# SD_Board.net
KiCad netlist of a schematic drawn in Altium Designer
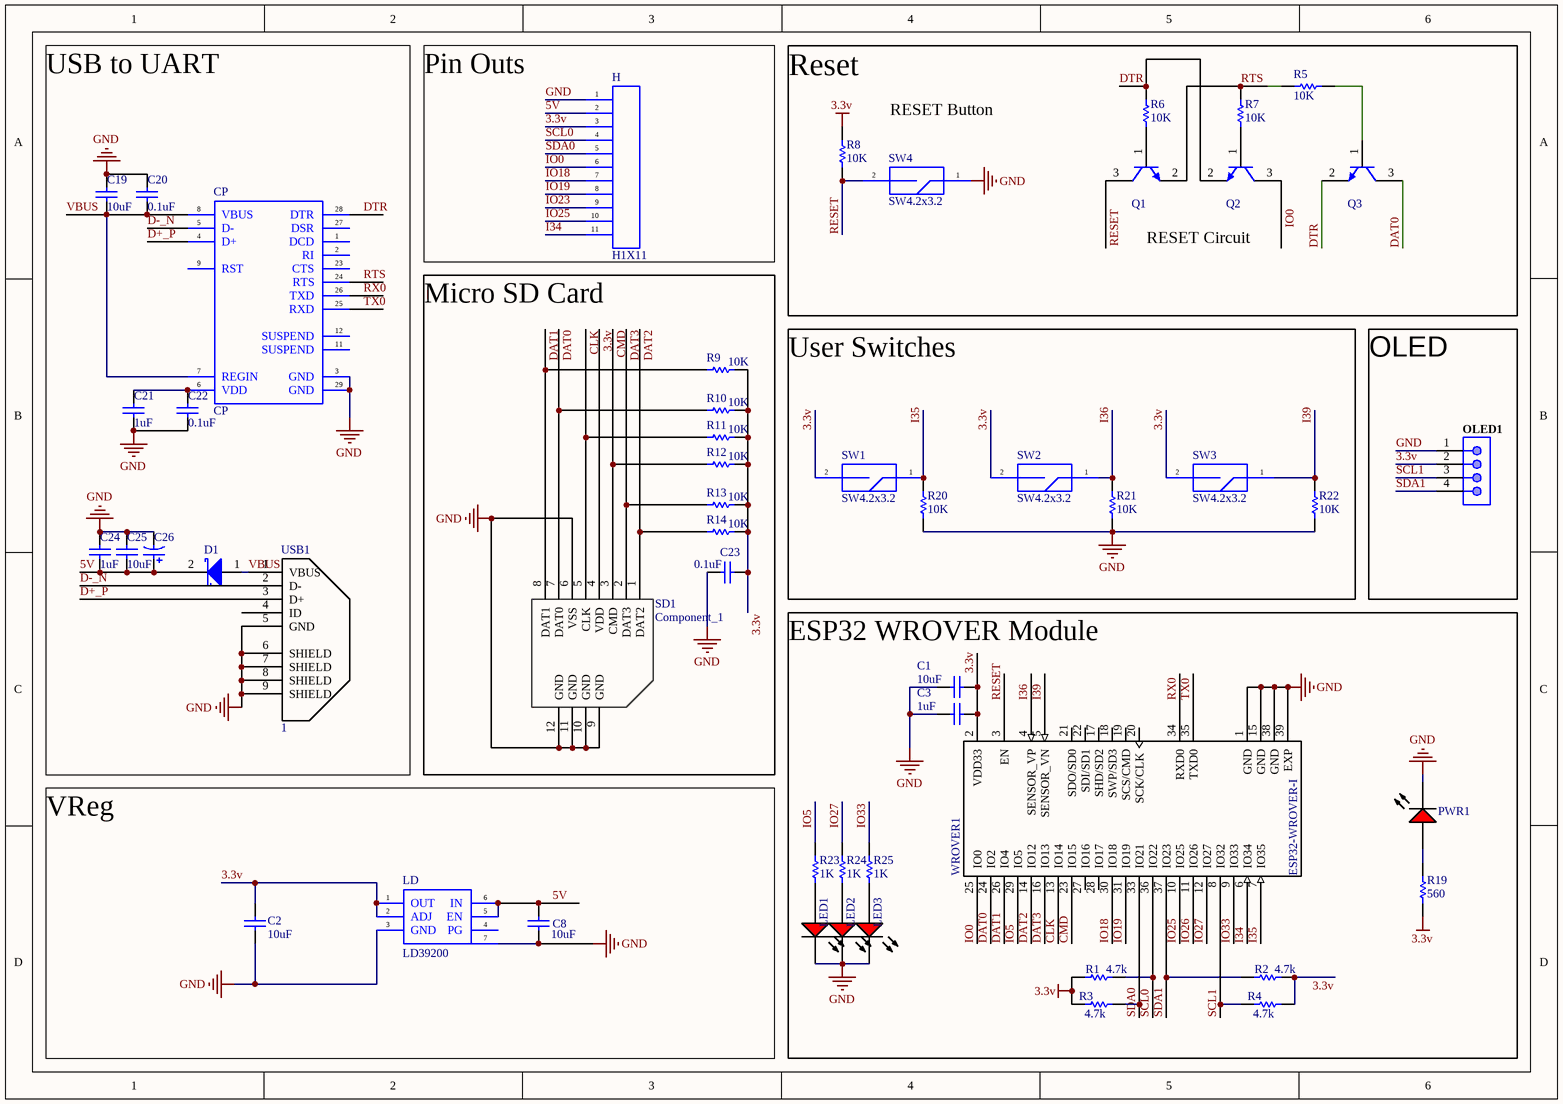
[diagram p0: SD_Board.SchDoc]

(export (version "E")
  (design (tool "Eeschema 10.0.6"))
  (components
    (comp (ref "C1")
      (value "10uF")
      (footprint "CAPC0402(1005)60_M")
      (description "CAP 10uF 6.3V ±0.5pF 0402 (1005 Metric) Thickness 0.6mm SMD")
      (fields (field (name "TOLERANCE") "Â±0.5pF"))
      (libsource (lib "Altium Content Vault") (part "CAP"))
    )
    (comp (ref "C2")
      (value "10uF")
      (footprint "CAPC1608X90X35NL15T15")
      (fields
        (field (name "MANUFACTURER") "AVX Interconnect / Elco")
        (field (name "PART NUMBER") "06035C271JAT2A")
      )
      (libsource (lib "Altium Content Vault") (part "CAP"))
    )
    (comp (ref "C3")
      (value "1uF")
      (footprint "CAPC0402(1005)60_M")
      (description "CAP 10uF 6.3V ±0.5pF 0402 (1005 Metric) Thickness 0.6mm SMD")
      (fields (field (name "TOLERANCE") "Â±0.5pF"))
      (libsource (lib "Altium Content Vault") (part "CAP"))
    )
    (comp (ref "C8")
      (value "10uF")
      (footprint "CAPC1608X90X35NL15T15")
      (fields
        (field (name "MANUFACTURER") "AVX Interconnect / Elco")
        (field (name "PART NUMBER") "06035C271JAT2A")
      )
      (libsource (lib "Altium Content Vault") (part "CAP"))
    )
    (comp (ref "C19")
      (value "10uF")
      (footprint "CAPC0402(1005)60_M")
      (description "CAP 10uF 6.3V ±0.5pF 0402 (1005 Metric) Thickness 0.6mm SMD")
      (fields (field (name "TOLERANCE") "Â±0.5pF"))
      (libsource (lib "Altium Content Vault") (part "CAP"))
    )
    (comp (ref "C20")
      (value "0.1uF")
      (footprint "CAPC0402(1005)60_M")
      (description "CAP .1uF 6.3V ±0.5pF 0402 (1005 Metric) Thickness 0.6mm SMD")
      (fields (field (name "TOLERANCE") "Â±0.5pF"))
      (libsource (lib "Altium Content Vault") (part "CAP"))
    )
    (comp (ref "C21")
      (value "1uF")
      (footprint "CAPC0402(1005)60_M")
      (description "CAP 10uF 6.3V ±0.5pF 0402 (1005 Metric) Thickness 0.6mm SMD")
      (fields (field (name "TOLERANCE") "Â±0.5pF"))
      (libsource (lib "Altium Content Vault") (part "CAP"))
    )
    (comp (ref "C22")
      (value "0.1uF")
      (footprint "CAPC0402(1005)60_M")
      (description "CAP .1uF 6.3V ±0.5pF 0402 (1005 Metric) Thickness 0.6mm SMD")
      (fields (field (name "TOLERANCE") "Â±0.5pF"))
      (libsource (lib "Altium Content Vault") (part "CAP"))
    )
    (comp (ref "C23")
      (value "0.1uF")
      (footprint "CAPC0402(1005)60_M")
      (description "CAP .1uF 6.3V ±0.5pF 0402 (1005 Metric) Thickness 0.6mm SMD")
      (fields (field (name "TOLERANCE") "Â±0.5pF"))
      (libsource (lib "Altium Content Vault") (part "CAP"))
    )
    (comp (ref "C24")
      (value "1uF")
      (footprint "CAPC0402(1005)60_M")
      (description "CAP 10uF 6.3V ±0.5pF 0402 (1005 Metric) Thickness 0.6mm SMD")
      (fields (field (name "TOLERANCE") "Â±0.5pF"))
      (libsource (lib "Altium Content Vault") (part "CAP"))
    )
    (comp (ref "C25")
      (value "10uF")
      (footprint "CAPC0402(1005)60_M")
      (description "CAP 10uF 6.3V ±0.5pF 0402 (1005 Metric) Thickness 0.6mm SMD")
      (fields (field (name "TOLERANCE") "Â±0.5pF"))
      (libsource (lib "Altium Content Vault") (part "CAP"))
    )
    (comp (ref "C26")
      (value "T491B105K025AT")
      (footprint "KEMT-T491-B_L")
      (description "Tantalum Capacitor, 1 uF, +/- 10%, 25 V, -55 to 125 degC, 1411 (3528 Metric), RoHS, Tape and Reel")
      (fields (field (name "MANUFACTURER") "Kemet") (field (name "VOLTAGE") "25VDC"))
      (libsource (lib "Altium Content Vault") (part "CAP-P-2"))
    )
    (comp (ref "CP") (value "CP") (footprint "CP2102:PCBComponent_1") (libsource (lib "CP2102") (part "CP")))
    (comp (ref "D1")
      (value "1N5819HW-7-F")
      (footprint "DIOD-SOD-123-2_V")
      (fields (field (name "MANUFACTURER") "Diodes Inc"))
      (libsource (lib "Altium Content Vault") (part "DIOD-DSKY-A1K2-2"))
    )
    (comp (ref "H")
      (value "H1X11")
      (footprint "H1X11:PCBComponent_1")
      (libsource (lib "H1X11") (part "H1X11"))
    )
    (comp (ref "LD")
      (value "LD39200")
      (footprint "LD39200:PCBComponent_1")
      (libsource (lib "LD39200") (part "LD39200"))
    )
    (comp (ref "LED1")
      (value "grn")
      (footprint "VISH-TLMX1100_V")
      (description "LED, RED, 2.1 V, -40 to 100 degC, 2-Pin SMD (0603), RoHS, Tape and Reel")
      (fields (field (name "TOLERANCE") "5%"))
      (libsource (lib "Altium Content Vault") (part "LED-RED-AK-2"))
    )
    (comp (ref "LED2")
      (value "grn")
      (footprint "VISH-TLMX1100_V")
      (description "LED, RED, 2.1 V, -40 to 100 degC, 2-Pin SMD (0603), RoHS, Tape and Reel")
      (fields (field (name "TOLERANCE") "5%"))
      (libsource (lib "Altium Content Vault") (part "LED-RED-AK-2"))
    )
    (comp (ref "LED3")
      (value "grn")
      (footprint "VISH-TLMX1100_V")
      (description "LED, RED, 2.1 V, -40 to 100 degC, 2-Pin SMD (0603), RoHS, Tape and Reel")
      (fields (field (name "TOLERANCE") "5%"))
      (libsource (lib "Altium Content Vault") (part "LED-RED-AK-2"))
    )
    (comp (ref "OLED1")
      (value "PH2541-4-SPGRH-6-3")
      (footprint "PCE-PH2541-4-SPGRH-6-3_V")
      (description "Male Header, Pitch 2.54 mm, 1x4 Position, Mated Height 6 mm, Tail Length 3 mm")
      (fields (field (name "MANUFACTURER") "Pinchao Electronic"))
      (libsource (lib "Altium Content Vault") (part "PCE-HDR-1P-M-R4"))
    )
    (comp (ref "PWR1")
      (value "grn")
      (footprint "VISH-TLMX1100_V")
      (description "LED, RED, 2.1 V, -40 to 100 degC, 2-Pin SMD (0603), RoHS, Tape and Reel")
      (fields (field (name "TOLERANCE") "5%"))
      (libsource (lib "Altium Content Vault") (part "LED-RED-AK-2"))
    )
    (comp (ref "Q1")
      (value "MMBT2222AWT1G")
      (footprint "ONSC-SC-70-3-419-04_V")
      (description "General Purpose Transistor, NPN Silicon, 3-Pin SC70, Pb-Free, Tape and Reel")
      (fields (field (name "MANUFACTURER") "On Semiconductor"))
      (libsource (lib "Altium Content Vault") (part "ONSC-NPN-B1E2C3-3"))
    )
    (comp (ref "Q2")
      (value "MMBT2222AWT1G")
      (footprint "ONSC-SC-70-3-419-04_V")
      (description "General Purpose Transistor, NPN Silicon, 3-Pin SC70, Pb-Free, Tape and Reel")
      (fields (field (name "MANUFACTURER") "On Semiconductor"))
      (libsource (lib "Altium Content Vault") (part "ONSC-NPN-B1E2C3-3"))
    )
    (comp (ref "Q3")
      (value "MMBT2222AWT1G")
      (footprint "ONSC-SC-70-3-419-04_V")
      (description "General Purpose Transistor, NPN Silicon, 3-Pin SC70, Pb-Free, Tape and Reel")
      (fields (field (name "MANUFACTURER") "On Semiconductor"))
      (libsource (lib "Altium Content Vault") (part "ONSC-NPN-B1E2C3-3"))
    )
    (comp (ref "R1")
      (value "4.7k")
      (footprint "RESC1608X55X30LL15T15")
      (description "Chip Resistor, 22 Ohm, +/- 1%, 0.1 W, -55 to 155 degC, 0603 (1608 Metric), RoHS, Tape and Reel")
      (libsource (lib "Altium Content Vault") (part "RES-2"))
    )
    (comp (ref "R2")
      (value "4.7k")
      (footprint "RESC1608X55X30LL15T15")
      (description "Chip Resistor, 22 Ohm, +/- 1%, 0.1 W, -55 to 155 degC, 0603 (1608 Metric), RoHS, Tape and Reel")
      (libsource (lib "Altium Content Vault") (part "RES-2"))
    )
    (comp (ref "R3")
      (value "4.7k")
      (footprint "RESC1608X55X30LL15T15")
      (description "Chip Resistor, 22 Ohm, +/- 1%, 0.1 W, -55 to 155 degC, 0603 (1608 Metric), RoHS, Tape and Reel")
      (libsource (lib "Altium Content Vault") (part "RES-2"))
    )
    (comp (ref "R4")
      (value "4.7k")
      (footprint "RESC1608X55X30LL15T15")
      (description "Chip Resistor, 22 Ohm, +/- 1%, 0.1 W, -55 to 155 degC, 0603 (1608 Metric), RoHS, Tape and Reel")
      (libsource (lib "Altium Content Vault") (part "RES-2"))
    )
    (comp (ref "R5")
      (value "10K")
      (footprint "RESC0402(1005)_M")
      (description "10K 0.063W 1% 0402 (1005 Metric)  SMD")
      (fields (field (name "TOLERANCE") "1 %") (field (name "POWER") "0.063 W"))
      (libsource (lib "Altium Content Vault") (part "RES"))
    )
    (comp (ref "R6")
      (value "10K")
      (footprint "RESC0402(1005)_M")
      (description "10K 0.063W 1% 0402 (1005 Metric)  SMD")
      (fields (field (name "TOLERANCE") "1 %") (field (name "POWER") "0.063 W"))
      (libsource (lib "Altium Content Vault") (part "RES"))
    )
    (comp (ref "R7")
      (value "10K")
      (footprint "RESC0402(1005)_M")
      (description "10K 0.063W 1% 0402 (1005 Metric)  SMD")
      (fields (field (name "TOLERANCE") "1 %") (field (name "POWER") "0.063 W"))
      (libsource (lib "Altium Content Vault") (part "RES"))
    )
    (comp (ref "R8")
      (value "10K")
      (footprint "RESC0402(1005)_M")
      (description "10K 0.063W 1% 0402 (1005 Metric)  SMD")
      (fields (field (name "TOLERANCE") "1 %") (field (name "POWER") "0.063 W"))
      (libsource (lib "Altium Content Vault") (part "RES"))
    )
    (comp (ref "R9")
      (value "10K")
      (footprint "RESC0402(1005)_M")
      (description "10K 0.063W 1% 0402 (1005 Metric)  SMD")
      (fields (field (name "TOLERANCE") "1 %") (field (name "POWER") "0.063 W"))
      (libsource (lib "Altium Content Vault") (part "RES"))
    )
    (comp (ref "R10")
      (value "10K")
      (footprint "RESC0402(1005)_M")
      (description "10K 0.063W 1% 0402 (1005 Metric)  SMD")
      (fields (field (name "TOLERANCE") "1 %") (field (name "POWER") "0.063 W"))
      (libsource (lib "Altium Content Vault") (part "RES"))
    )
    (comp (ref "R11")
      (value "10K")
      (footprint "RESC0402(1005)_M")
      (description "10K 0.063W 1% 0402 (1005 Metric)  SMD")
      (fields (field (name "TOLERANCE") "1 %") (field (name "POWER") "0.063 W"))
      (libsource (lib "Altium Content Vault") (part "RES"))
    )
    (comp (ref "R12")
      (value "10K")
      (footprint "RESC0402(1005)_M")
      (description "10K 0.063W 1% 0402 (1005 Metric)  SMD")
      (fields (field (name "TOLERANCE") "1 %") (field (name "POWER") "0.063 W"))
      (libsource (lib "Altium Content Vault") (part "RES"))
    )
    (comp (ref "R13")
      (value "10K")
      (footprint "RESC0402(1005)_M")
      (description "10K 0.063W 1% 0402 (1005 Metric)  SMD")
      (fields (field (name "TOLERANCE") "1 %") (field (name "POWER") "0.063 W"))
      (libsource (lib "Altium Content Vault") (part "RES"))
    )
    (comp (ref "R14")
      (value "10K")
      (footprint "RESC0402(1005)_M")
      (description "10K 0.063W 1% 0402 (1005 Metric)  SMD")
      (fields (field (name "TOLERANCE") "1 %") (field (name "POWER") "0.063 W"))
      (libsource (lib "Altium Content Vault") (part "RES"))
    )
    (comp (ref "R19")
      (value "560")
      (footprint "RESC0402(1005)_M")
      (description "560R 0.063W 1% 0402 (1005 Metric)  SMD")
      (fields (field (name "TOLERANCE") "1 %") (field (name "POWER") "0.063 W"))
      (libsource (lib "Altium Content Vault") (part "RES"))
    )
    (comp (ref "R20")
      (value "10K")
      (footprint "RESC0402(1005)_M")
      (description "10K 0.063W 1% 0402 (1005 Metric)  SMD")
      (fields (field (name "TOLERANCE") "1 %") (field (name "POWER") "0.063 W"))
      (libsource (lib "Altium Content Vault") (part "RES"))
    )
    (comp (ref "R21")
      (value "10K")
      (footprint "RESC0402(1005)_M")
      (description "10K 0.063W 1% 0402 (1005 Metric)  SMD")
      (fields (field (name "TOLERANCE") "1 %") (field (name "POWER") "0.063 W"))
      (libsource (lib "Altium Content Vault") (part "RES"))
    )
    (comp (ref "R22")
      (value "10K")
      (footprint "RESC0402(1005)_M")
      (description "10K 0.063W 1% 0402 (1005 Metric)  SMD")
      (fields (field (name "TOLERANCE") "1 %") (field (name "POWER") "0.063 W"))
      (libsource (lib "Altium Content Vault") (part "RES"))
    )
    (comp (ref "R23")
      (value "1K")
      (footprint "RESC0402(1005)_M")
      (description "10K 0.063W 1% 0402 (1005 Metric)  SMD")
      (fields (field (name "TOLERANCE") "1 %") (field (name "POWER") "0.063 W"))
      (libsource (lib "Altium Content Vault") (part "RES"))
    )
    (comp (ref "R24")
      (value "1K")
      (footprint "RESC0402(1005)_M")
      (description "10K 0.063W 1% 0402 (1005 Metric)  SMD")
      (fields (field (name "TOLERANCE") "1 %") (field (name "POWER") "0.063 W"))
      (libsource (lib "Altium Content Vault") (part "RES"))
    )
    (comp (ref "R25")
      (value "1K")
      (footprint "RESC0402(1005)_M")
      (description "10K 0.063W 1% 0402 (1005 Metric)  SMD")
      (fields (field (name "TOLERANCE") "1 %") (field (name "POWER") "0.063 W"))
      (libsource (lib "Altium Content Vault") (part "RES"))
    )
    (comp (ref "SD1")
      (value "Component_1")
      (footprint "SD_Amphenol")
      (libsource (lib "Amphenol2") (part "Component_1"))
    )
    (comp (ref "SW1")
      (value "SW4.2x3.2")
      (footprint "Switch4.2x3.2")
      (libsource (lib "Switch4.2x3.2") (part "SW4.2x3.2"))
    )
    (comp (ref "SW2")
      (value "SW4.2x3.2")
      (footprint "Switch4.2x3.2")
      (libsource (lib "Switch4.2x3.2") (part "SW4.2x3.2"))
    )
    (comp (ref "SW3")
      (value "SW4.2x3.2")
      (footprint "Switch4.2x3.2")
      (libsource (lib "Switch4.2x3.2") (part "SW4.2x3.2"))
    )
    (comp (ref "SW4")
      (value "SW4.2x3.2")
      (footprint "Switch4.2x3.2")
      (libsource (lib "Switch4.2x3.2") (part "SW4.2x3.2"))
    )
    (comp (ref "USB1")
      (value "1")
      (footprint "Amphenol_USB:PCBComponent_1")
      (libsource (lib "Amphenol_USB") (part "Component_1"))
    )
    (comp (ref "WROVER1")
      (value "ESP32-WROVER-I")
      (footprint "XCVR_ESP32-WROVER-I")
      (description "Module: combo; GPIO, I2C x2, I2S x2, SDIO, SPI x3, UART x3; U.FL")
      (fields (field (name "DIGI-KEY_PART_NUMBER") "1904-1008-1-ND") (field (name "MF") "Espressif Systems"))
      (libsource (lib "ESP32-WROVER-I") (part "ESP32-WROVER-I"))
    )
  )
  (nets
    (net (code "1") (name "/5V") (class "Default")
      (node (ref "C24") (pin "1") (pinfunction "1_1") (pintype "passive"))
      (node (ref "C25") (pin "1") (pinfunction "1_1") (pintype "passive"))
      (node (ref "C26") (pin "1") (pinfunction "1_1") (pintype "passive"))
      (node (ref "C8") (pin "1") (pinfunction "1_1") (pintype "passive"))
      (node (ref "D1") (pin "2") (pinfunction "K_2") (pintype "passive"))
      (node (ref "H") (pin "2") (pinfunction "2_2") (pintype "passive"))
      (node (ref "LD") (pin "5") (pinfunction "EN_5") (pintype "passive"))
      (node (ref "LD") (pin "6") (pinfunction "IN_6") (pintype "passive"))
    )
    (net (code "2") (name "/CLK") (class "Default")
      (node (ref "R11") (pin "1") (pinfunction "1_1") (pintype "passive"))
      (node (ref "SD1") (pin "5") (pinfunction "CLK_5") (pintype "passive"))
      (node (ref "WROVER1") (pin "13") (pinfunction "IO14_13") (pintype "bidirectional"))
    )
    (net (code "3") (name "/CMD") (class "Default")
      (node (ref "R12") (pin "1") (pinfunction "1_1") (pintype "passive"))
      (node (ref "SD1") (pin "3") (pinfunction "CMD_3") (pintype "passive"))
      (node (ref "WROVER1") (pin "23") (pinfunction "IO15_23") (pintype "bidirectional"))
    )
    (net (code "4") (name "/D+_P") (class "Default")
      (node (ref "CP") (pin "4") (pinfunction "D+_4") (pintype "passive"))
      (node (ref "USB1") (pin "3") (pinfunction "D+_3") (pintype "passive"))
    )
    (net (code "5") (name "/D-_N") (class "Default")
      (node (ref "CP") (pin "5") (pinfunction "D-_5") (pintype "passive"))
      (node (ref "USB1") (pin "2") (pinfunction "D-_2") (pintype "passive"))
    )
    (net (code "6") (name "/DAT0") (class "Default")
      (node (ref "Q3") (pin "3") (pinfunction "C_3") (pintype "passive"))
      (node (ref "R10") (pin "1") (pinfunction "1_1") (pintype "passive"))
      (node (ref "SD1") (pin "7") (pinfunction "DAT0_7") (pintype "passive"))
      (node (ref "WROVER1") (pin "24") (pinfunction "IO2_24") (pintype "bidirectional"))
    )
    (net (code "7") (name "/DAT1") (class "Default")
      (node (ref "R9") (pin "1") (pinfunction "1_1") (pintype "passive"))
      (node (ref "SD1") (pin "8") (pinfunction "DAT1_8") (pintype "passive"))
      (node (ref "WROVER1") (pin "26") (pinfunction "IO4_26") (pintype "bidirectional"))
    )
    (net (code "8") (name "/DAT2") (class "Default")
      (node (ref "R14") (pin "1") (pinfunction "1_1") (pintype "passive"))
      (node (ref "SD1") (pin "1") (pinfunction "DAT2_1") (pintype "passive"))
      (node (ref "WROVER1") (pin "14") (pinfunction "IO12_14") (pintype "bidirectional"))
    )
    (net (code "9") (name "/DAT3") (class "Default")
      (node (ref "R13") (pin "1") (pinfunction "1_1") (pintype "passive"))
      (node (ref "SD1") (pin "2") (pinfunction "DAT3_2") (pintype "passive"))
      (node (ref "WROVER1") (pin "16") (pinfunction "IO13_16") (pintype "bidirectional"))
    )
    (net (code "10") (name "/DTR") (class "Default")
      (node (ref "CP") (pin "28") (pinfunction "DTR_28") (pintype "passive"))
      (node (ref "Q2") (pin "2") (pinfunction "E_2") (pintype "passive"))
      (node (ref "Q3") (pin "2") (pinfunction "E_2") (pintype "passive"))
      (node (ref "R6") (pin "2") (pinfunction "2_2") (pintype "passive"))
    )
    (net (code "11") (name "/I34") (class "Default")
      (node (ref "H") (pin "11") (pinfunction "11_11") (pintype "passive"))
      (node (ref "WROVER1") (pin "6") (pinfunction "IO34_6") (pintype "input"))
    )
    (net (code "12") (name "/I35") (class "Default")
      (node (ref "R20") (pin "2") (pinfunction "2_2") (pintype "passive"))
      (node (ref "SW1") (pin "1") (pinfunction "1_1") (pintype "passive"))
      (node (ref "WROVER1") (pin "7") (pinfunction "IO35_7") (pintype "input"))
    )
    (net (code "13") (name "/I36") (class "Default")
      (node (ref "R21") (pin "2") (pinfunction "2_2") (pintype "passive"))
      (node (ref "SW2") (pin "1") (pinfunction "1_1") (pintype "passive"))
      (node (ref "WROVER1") (pin "4") (pinfunction "SENSOR_VP_4") (pintype "input"))
    )
    (net (code "14") (name "/I39") (class "Default")
      (node (ref "R22") (pin "2") (pinfunction "2_2") (pintype "passive"))
      (node (ref "SW3") (pin "1") (pinfunction "1_1") (pintype "passive"))
      (node (ref "WROVER1") (pin "5") (pinfunction "SENSOR_VN_5") (pintype "input"))
    )
    (net (code "15") (name "/IO0") (class "Default")
      (node (ref "H") (pin "6") (pinfunction "6_6") (pintype "passive"))
      (node (ref "Q2") (pin "3") (pinfunction "C_3") (pintype "passive"))
      (node (ref "WROVER1") (pin "25") (pinfunction "IO0_25") (pintype "bidirectional"))
    )
    (net (code "16") (name "/IO5") (class "Default")
      (node (ref "R23") (pin "1") (pinfunction "1_1") (pintype "passive"))
      (node (ref "WROVER1") (pin "29") (pinfunction "IO5_29") (pintype "bidirectional"))
    )
    (net (code "17") (name "/IO18") (class "Default")
      (node (ref "H") (pin "7") (pinfunction "7_7") (pintype "passive"))
      (node (ref "WROVER1") (pin "30") (pinfunction "IO18_30") (pintype "bidirectional"))
    )
    (net (code "18") (name "/IO19") (class "Default")
      (node (ref "H") (pin "8") (pinfunction "8_8") (pintype "passive"))
      (node (ref "WROVER1") (pin "31") (pinfunction "IO19_31") (pintype "bidirectional"))
    )
    (net (code "19") (name "/IO23") (class "Default")
      (node (ref "H") (pin "9") (pinfunction "9_9") (pintype "passive"))
    )
    (net (code "20") (name "/IO25") (class "Default")
      (node (ref "H") (pin "10") (pinfunction "10_10") (pintype "passive"))
      (node (ref "WROVER1") (pin "10") (pinfunction "IO25_10") (pintype "bidirectional"))
    )
    (net (code "21") (name "/IO26") (class "Default")
      (node (ref "WROVER1") (pin "11") (pinfunction "IO26_11") (pintype "bidirectional"))
    )
    (net (code "22") (name "/IO27") (class "Default")
      (node (ref "R24") (pin "1") (pinfunction "1_1") (pintype "passive"))
      (node (ref "WROVER1") (pin "12") (pinfunction "IO27_12") (pintype "bidirectional"))
    )
    (net (code "23") (name "/IO33") (class "Default")
      (node (ref "R25") (pin "1") (pinfunction "1_1") (pintype "passive"))
      (node (ref "WROVER1") (pin "9") (pinfunction "IO33_9") (pintype "bidirectional"))
    )
    (net (code "24") (name "/RESET") (class "Default")
      (node (ref "Q1") (pin "3") (pinfunction "C_3") (pintype "passive"))
      (node (ref "R8") (pin "2") (pinfunction "2_2") (pintype "passive"))
      (node (ref "SW4") (pin "2") (pinfunction "2_2") (pintype "passive"))
      (node (ref "WROVER1") (pin "3") (pinfunction "EN_3") (pintype "bidirectional"))
    )
    (net (code "25") (name "/RTS") (class "Default")
      (node (ref "CP") (pin "24") (pinfunction "RTS_24") (pintype "passive"))
      (node (ref "Q1") (pin "2") (pinfunction "E_2") (pintype "passive"))
      (node (ref "R5") (pin "2") (pinfunction "2_2") (pintype "passive"))
      (node (ref "R7") (pin "2") (pinfunction "2_2") (pintype "passive"))
    )
    (net (code "26") (name "/RX0") (class "Default")
      (node (ref "CP") (pin "26") (pinfunction "TXD_26") (pintype "passive"))
      (node (ref "WROVER1") (pin "34") (pinfunction "RXD0_34") (pintype "bidirectional"))
    )
    (net (code "27") (name "/SCL0") (class "Default")
      (node (ref "H") (pin "4") (pinfunction "4_4") (pintype "passive"))
      (node (ref "R1") (pin "1") (pinfunction "1_1") (pintype "passive"))
      (node (ref "WROVER1") (pin "36") (pinfunction "IO22_36") (pintype "bidirectional"))
    )
    (net (code "28") (name "/SCL1") (class "Default")
      (node (ref "OLED1") (pin "3") (pinfunction "3_3") (pintype "passive"))
      (node (ref "R4") (pin "1") (pinfunction "1_1") (pintype "passive"))
      (node (ref "WROVER1") (pin "8") (pinfunction "IO32_8") (pintype "bidirectional"))
    )
    (net (code "29") (name "/SDA0") (class "Default")
      (node (ref "H") (pin "5") (pinfunction "5_5") (pintype "passive"))
      (node (ref "R3") (pin "1") (pinfunction "1_1") (pintype "passive"))
      (node (ref "WROVER1") (pin "33") (pinfunction "IO21_33") (pintype "bidirectional"))
    )
    (net (code "30") (name "/SDA1") (class "Default")
      (node (ref "OLED1") (pin "4") (pinfunction "4_4") (pintype "passive"))
      (node (ref "R2") (pin "1") (pinfunction "1_1") (pintype "passive"))
      (node (ref "WROVER1") (pin "37") (pinfunction "IO23_37") (pintype "bidirectional"))
    )
    (net (code "31") (name "/TX0") (class "Default")
      (node (ref "CP") (pin "25") (pinfunction "RXD_25") (pintype "passive"))
      (node (ref "WROVER1") (pin "35") (pinfunction "TXD0_35") (pintype "bidirectional"))
    )
    (net (code "32") (name "/VBUS") (class "Default")
      (node (ref "C19") (pin "1") (pinfunction "1_1") (pintype "passive"))
      (node (ref "C20") (pin "1") (pinfunction "1_1") (pintype "passive"))
      (node (ref "CP") (pin "7") (pinfunction "REGIN_7") (pintype "passive"))
      (node (ref "CP") (pin "8") (pinfunction "VBUS_8") (pintype "passive"))
      (node (ref "D1") (pin "1") (pinfunction "A_1") (pintype "passive"))
      (node (ref "USB1") (pin "1") (pinfunction "VBUS_1") (pintype "passive"))
    )
    (net (code "33") (name "3.3v") (class "Default")
      (node (ref "C1") (pin "1") (pinfunction "1_1") (pintype "passive"))
      (node (ref "C2") (pin "2") (pinfunction "2_2") (pintype "passive"))
      (node (ref "C23") (pin "1") (pinfunction "1_1") (pintype "passive"))
      (node (ref "C3") (pin "1") (pinfunction "1_1") (pintype "passive"))
      (node (ref "H") (pin "3") (pinfunction "3_3") (pintype "passive"))
      (node (ref "LD") (pin "1") (pinfunction "OUT_1") (pintype "passive"))
      (node (ref "LD") (pin "2") (pinfunction "ADJ_2") (pintype "passive"))
      (node (ref "OLED1") (pin "2") (pinfunction "2_2") (pintype "passive"))
      (node (ref "R1") (pin "2") (pinfunction "2_2") (pintype "passive"))
      (node (ref "R10") (pin "2") (pinfunction "2_2") (pintype "passive"))
      (node (ref "R11") (pin "2") (pinfunction "2_2") (pintype "passive"))
      (node (ref "R12") (pin "2") (pinfunction "2_2") (pintype "passive"))
      (node (ref "R13") (pin "2") (pinfunction "2_2") (pintype "passive"))
      (node (ref "R14") (pin "2") (pinfunction "2_2") (pintype "passive"))
      (node (ref "R19") (pin "1") (pinfunction "1_1") (pintype "passive"))
      (node (ref "R2") (pin "2") (pinfunction "2_2") (pintype "passive"))
      (node (ref "R3") (pin "2") (pinfunction "2_2") (pintype "passive"))
      (node (ref "R4") (pin "2") (pinfunction "2_2") (pintype "passive"))
      (node (ref "R8") (pin "1") (pinfunction "1_1") (pintype "passive"))
      (node (ref "R9") (pin "2") (pinfunction "2_2") (pintype "passive"))
      (node (ref "SD1") (pin "4") (pinfunction "VDD_4") (pintype "passive"))
      (node (ref "SW1") (pin "2") (pinfunction "2_2") (pintype "passive"))
      (node (ref "SW2") (pin "2") (pinfunction "2_2") (pintype "passive"))
      (node (ref "SW3") (pin "2") (pinfunction "2_2") (pintype "passive"))
      (node (ref "WROVER1") (pin "2") (pinfunction "VDD33_2") (pintype "power_in"))
    )
    (net (code "34") (name "GND") (class "Default")
      (node (ref "C1") (pin "2") (pinfunction "2_2") (pintype "passive"))
      (node (ref "C19") (pin "2") (pinfunction "2_2") (pintype "passive"))
      (node (ref "C2") (pin "1") (pinfunction "1_1") (pintype "passive"))
      (node (ref "C20") (pin "2") (pinfunction "2_2") (pintype "passive"))
      (node (ref "C21") (pin "1") (pinfunction "1_1") (pintype "passive"))
      (node (ref "C22") (pin "1") (pinfunction "1_1") (pintype "passive"))
      (node (ref "C23") (pin "2") (pinfunction "2_2") (pintype "passive"))
      (node (ref "C24") (pin "2") (pinfunction "2_2") (pintype "passive"))
      (node (ref "C25") (pin "2") (pinfunction "2_2") (pintype "passive"))
      (node (ref "C26") (pin "2") (pinfunction "2_2") (pintype "passive"))
      (node (ref "C3") (pin "2") (pinfunction "2_2") (pintype "passive"))
      (node (ref "C8") (pin "2") (pinfunction "2_2") (pintype "passive"))
      (node (ref "CP") (pin "29") (pinfunction "GND_29") (pintype "passive"))
      (node (ref "CP") (pin "3") (pinfunction "GND_3") (pintype "passive"))
      (node (ref "H") (pin "1") (pinfunction "1_1") (pintype "passive"))
      (node (ref "LD") (pin "3") (pinfunction "GND_3") (pintype "passive"))
      (node (ref "LD") (pin "7") (pinfunction "PAD_7") (pintype "passive"))
      (node (ref "LED1") (pin "2") (pinfunction "K_2") (pintype "passive"))
      (node (ref "LED2") (pin "2") (pinfunction "K_2") (pintype "passive"))
      (node (ref "LED3") (pin "2") (pinfunction "K_2") (pintype "passive"))
      (node (ref "OLED1") (pin "1") (pinfunction "1_1") (pintype "passive"))
      (node (ref "PWR1") (pin "2") (pinfunction "K_2") (pintype "passive"))
      (node (ref "R20") (pin "1") (pinfunction "1_1") (pintype "passive"))
      (node (ref "R21") (pin "1") (pinfunction "1_1") (pintype "passive"))
      (node (ref "R22") (pin "1") (pinfunction "1_1") (pintype "passive"))
      (node (ref "SD1") (pin "10") (pinfunction "GND_10") (pintype "passive"))
      (node (ref "SD1") (pin "11") (pinfunction "GND_11") (pintype "passive"))
      (node (ref "SD1") (pin "12") (pinfunction "GND_12") (pintype "passive"))
      (node (ref "SD1") (pin "6") (pinfunction "VSS_6") (pintype "passive"))
      (node (ref "SD1") (pin "9") (pinfunction "GND_9") (pintype "passive"))
      (node (ref "SW4") (pin "1") (pinfunction "1_1") (pintype "passive"))
      (node (ref "USB1") (pin "5") (pinfunction "GND_5") (pintype "passive"))
      (node (ref "USB1") (pin "6") (pinfunction "SHIELD_6") (pintype "passive"))
      (node (ref "USB1") (pin "7") (pinfunction "SHIELD_7") (pintype "passive"))
      (node (ref "USB1") (pin "8") (pinfunction "SHIELD_8") (pintype "passive"))
      (node (ref "USB1") (pin "9") (pinfunction "SHIELD_9") (pintype "passive"))
      (node (ref "WROVER1") (pin "1") (pinfunction "GND_1") (pintype "power_in"))
      (node (ref "WROVER1") (pin "15") (pinfunction "GND_15") (pintype "power_in"))
      (node (ref "WROVER1") (pin "38") (pinfunction "GND_38") (pintype "power_in"))
      (node (ref "WROVER1") (pin "39") (pinfunction "EXP_39") (pintype "power_in"))
    )
    (net (code "35") (name "Net-(CP-VDD)") (class "Default")
      (node (ref "C21") (pin "2") (pinfunction "2_2") (pintype "passive"))
      (node (ref "C22") (pin "2") (pinfunction "2_2") (pintype "passive"))
      (node (ref "CP") (pin "6") (pinfunction "VDD_6") (pintype "passive"))
    )
    (net (code "36") (name "Net-(LED1-A)") (class "Default")
      (node (ref "LED1") (pin "1") (pinfunction "A_1") (pintype "passive"))
      (node (ref "R23") (pin "2") (pinfunction "2_2") (pintype "passive"))
    )
    (net (code "37") (name "Net-(LED2-A)") (class "Default")
      (node (ref "LED2") (pin "1") (pinfunction "A_1") (pintype "passive"))
      (node (ref "R24") (pin "2") (pinfunction "2_2") (pintype "passive"))
    )
    (net (code "38") (name "Net-(LED3-A)") (class "Default")
      (node (ref "LED3") (pin "1") (pinfunction "A_1") (pintype "passive"))
      (node (ref "R25") (pin "2") (pinfunction "2_2") (pintype "passive"))
    )
    (net (code "39") (name "Net-(PWR1-A)") (class "Default")
      (node (ref "PWR1") (pin "1") (pinfunction "A_1") (pintype "passive"))
      (node (ref "R19") (pin "2") (pinfunction "2_2") (pintype "passive"))
    )
    (net (code "40") (name "Net-(Q1-B)") (class "Default")
      (node (ref "Q1") (pin "1") (pinfunction "B_1") (pintype "passive"))
      (node (ref "R6") (pin "1") (pinfunction "1_1") (pintype "passive"))
    )
    (net (code "41") (name "Net-(Q2-B)") (class "Default")
      (node (ref "Q2") (pin "1") (pinfunction "B_1") (pintype "passive"))
      (node (ref "R7") (pin "1") (pinfunction "1_1") (pintype "passive"))
    )
    (net (code "42") (name "Net-(Q3-B)") (class "Default")
      (node (ref "Q3") (pin "1") (pinfunction "B_1") (pintype "passive"))
      (node (ref "R5") (pin "1") (pinfunction "1_1") (pintype "passive"))
    )
    (net (code "43") (name "unconnected-(CP-CTS-Pad23)") (class "Default")
      (node (ref "CP") (pin "23") (pinfunction "CTS_23") (pintype "passive"))
    )
    (net (code "44") (name "unconnected-(CP-DCD-Pad1)") (class "Default")
      (node (ref "CP") (pin "1") (pinfunction "DCD_1") (pintype "passive"))
    )
    (net (code "45") (name "unconnected-(CP-DSR-Pad27)") (class "Default")
      (node (ref "CP") (pin "27") (pinfunction "DSR_27") (pintype "passive"))
    )
    (net (code "46") (name "unconnected-(CP-RI-Pad2)") (class "Default")
      (node (ref "CP") (pin "2") (pinfunction "RI_2") (pintype "passive"))
    )
    (net (code "47") (name "unconnected-(CP-RST-Pad9)") (class "Default")
      (node (ref "CP") (pin "9") (pinfunction "RST_9") (pintype "passive"))
    )
    (net (code "48") (name "unconnected-(CP-SUSPEND-Pad11)") (class "Default")
      (node (ref "CP") (pin "11") (pinfunction "SUSPEND_11") (pintype "passive"))
    )
    (net (code "49") (name "unconnected-(CP-SUSPEND-Pad12)") (class "Default")
      (node (ref "CP") (pin "12") (pinfunction "SUSPEND_12") (pintype "passive"))
    )
    (net (code "50") (name "unconnected-(LD-PG-Pad4)") (class "Default")
      (node (ref "LD") (pin "4") (pinfunction "PG_4") (pintype "passive"))
    )
    (net (code "51") (name "unconnected-(USB1-ID-Pad4)") (class "Default")
      (node (ref "USB1") (pin "4") (pinfunction "ID_4") (pintype "passive"))
    )
    (net (code "52") (name "unconnected-(WROVER1-IO16-Pad27)") (class "Default")
      (node (ref "WROVER1") (pin "27") (pinfunction "IO16_27") (pintype "bidirectional"))
    )
    (net (code "53") (name "unconnected-(WROVER1-IO17-Pad28)") (class "Default")
      (node (ref "WROVER1") (pin "28") (pinfunction "IO17_28") (pintype "bidirectional"))
    )
    (net (code "54") (name "unconnected-(WROVER1-SCK{slash}CLK-Pad20)") (class "Default")
      (node (ref "WROVER1") (pin "20") (pinfunction "SCK/CLK_20") (pintype "bidirectional"))
    )
    (net (code "55") (name "unconnected-(WROVER1-SCS{slash}CMD-Pad19)") (class "Default")
      (node (ref "WROVER1") (pin "19") (pinfunction "SCS/CMD_19") (pintype "bidirectional"))
    )
    (net (code "56") (name "unconnected-(WROVER1-SDI{slash}SD1-Pad22)") (class "Default")
      (node (ref "WROVER1") (pin "22") (pinfunction "SDI/SD1_22") (pintype "bidirectional"))
    )
    (net (code "57") (name "unconnected-(WROVER1-SDO{slash}SD0-Pad21)") (class "Default")
      (node (ref "WROVER1") (pin "21") (pinfunction "SDO/SD0_21") (pintype "bidirectional"))
    )
    (net (code "58") (name "unconnected-(WROVER1-SHD{slash}SD2-Pad17)") (class "Default")
      (node (ref "WROVER1") (pin "17") (pinfunction "SHD/SD2_17") (pintype "bidirectional"))
    )
    (net (code "59") (name "unconnected-(WROVER1-SWP{slash}SD3-Pad18)") (class "Default")
      (node (ref "WROVER1") (pin "18") (pinfunction "SWP/SD3_18") (pintype "bidirectional"))
    )
  )
)
